# PX4FMUv2_4_6_0.net
KiCad netlist of a schematic drawn in Altium Designer
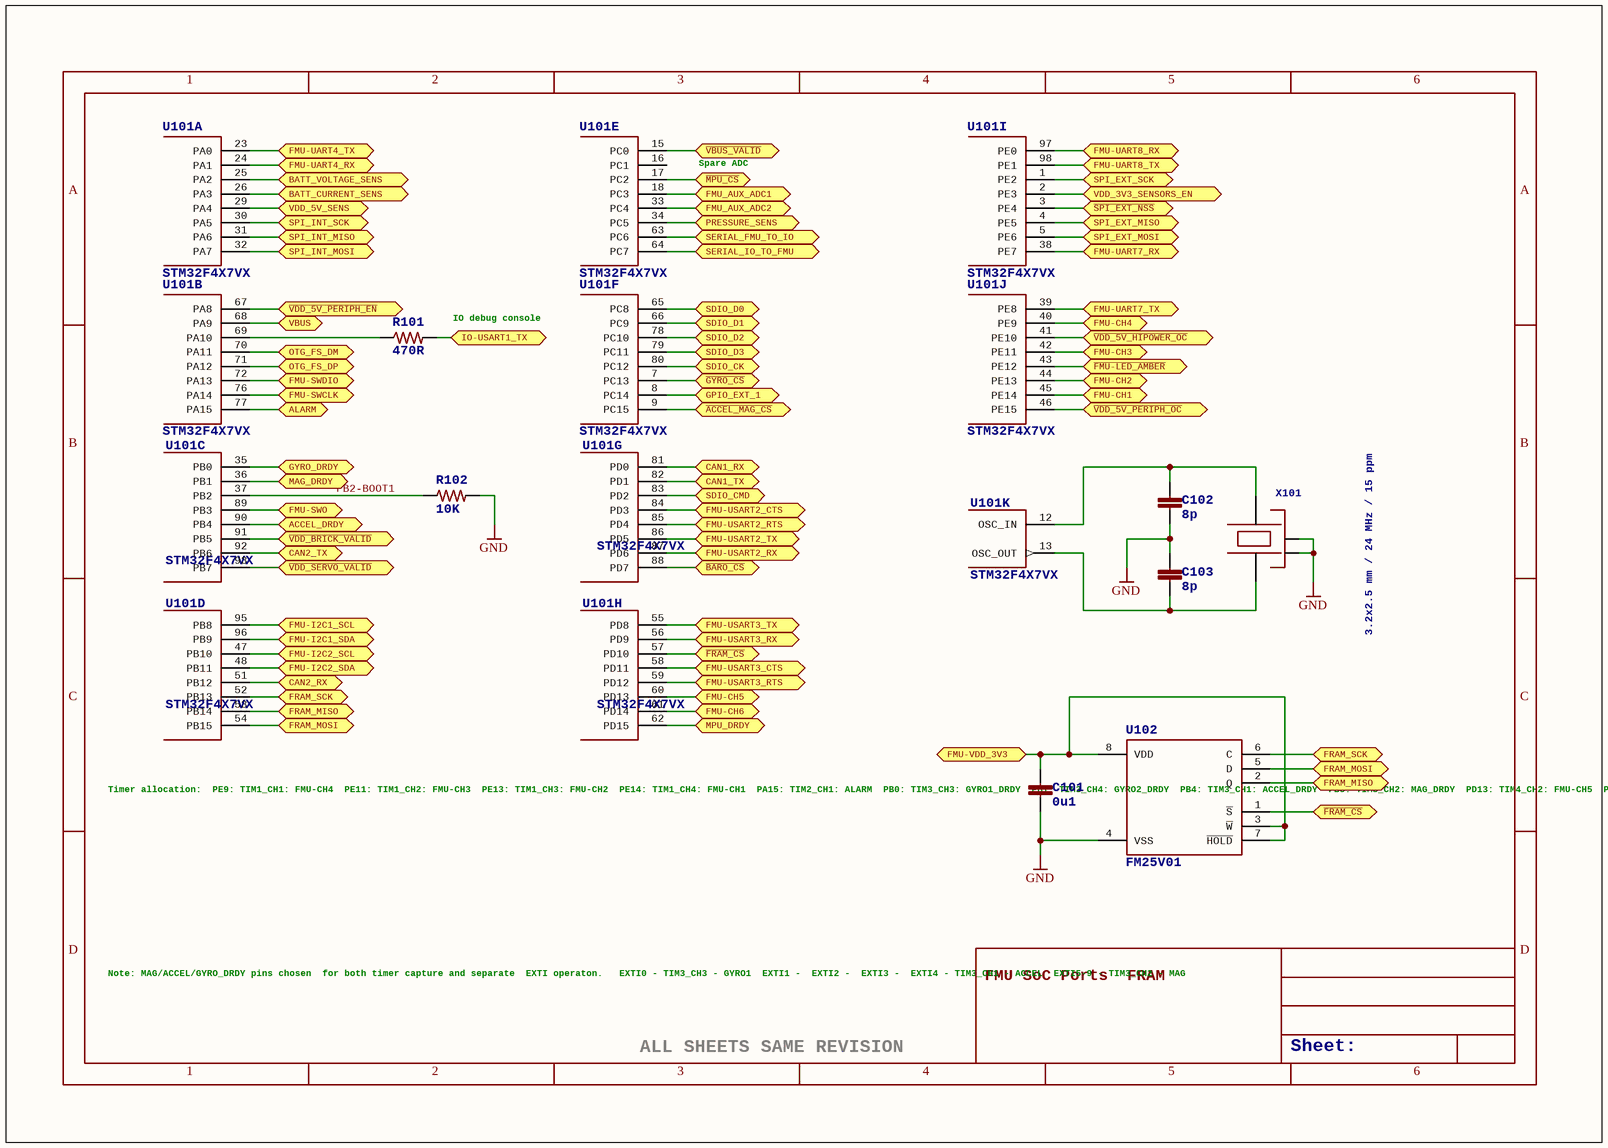
[diagram p0: PX4FMUv2.4.6_0.SchDoc]

(export (version "E")
  (design (tool "Eeschema 10.0.6"))
  (components
    (comp (ref "C101")
      (value "0u1")
      (footprint "0402-CAP")
      (description "CapacitorStandard 0603 ceramic capacitor, and 0.1\" leaded capacitor.")
      (fields (field (name "PARTNO") "CC0402ZRY5V7BB104"))
      (libsource (lib "pixhawk2") (part "CAP0402"))
    )
    (comp (ref "C102")
      (value "8p")
      (footprint "0402-CAP")
      (description "CapacitorStandard 0603 ceramic capacitor, and 0.1\" leaded capacitor.")
      (fields (field (name "PARTNO") "C1005C0G1H080C"))
      (libsource (lib "pixhawk2") (part "CAP0402"))
    )
    (comp (ref "C103")
      (value "8p")
      (footprint "0402-CAP")
      (description "CapacitorStandard 0603 ceramic capacitor, and 0.1\" leaded capacitor.")
      (fields (field (name "PARTNO") "C1005C0G1H080C"))
      (libsource (lib "pixhawk2") (part "CAP0402"))
    )
    (comp (ref "R101")
      (value "470R")
      (footprint "0402-RES")
      (fields (field (name "PARTNO") "RC0402FR-07470RL"))
      (libsource (lib "pixhawk2") (part "RESISTOR0402-RES"))
    )
    (comp (ref "R102")
      (value "10K")
      (footprint "0402-RES")
      (fields (field (name "PARTNO") "RC0402FR-0710KL"))
      (libsource (lib "pixhawk2") (part "RESISTOR0402-RES"))
    )
    (comp (ref "U101")
      (value "STM32F4X7VX")
      (footprint "TQFP100")
      (fields (field (name "PARTNO") "STM32F427VI"))
      (libsource (lib "pixhawk2") (part "STM32F4X7VX"))
    )
    (comp (ref "U102")
      (value "FM25V01")
      (footprint "SO08")
      (description "FM25V01 128Kb Serial 3V F-RAM Memory")
      (fields (field (name "PARTNO") "FM25V01-G"))
      (libsource (lib "pixhawk2") (part "FM25V01"))
    )
    (comp (ref "X101")
      (value "3.2x2.5 mm / 24 MHz / 15 ppm")
      (footprint "OSCILLATOR-3.2X2.5")
      (description "Crystal Oscillator in 3.2x2.5 SMD")
      (libsource (lib "pixhawk2") (part "OSCILLATOR-3.2X2.5"))
    )
  )
  (nets
    (net (code "1") (name "/ACCEL_DRDY") (class "Default")
      (node (ref "U101") (pin "90") (pinfunction "PB4_90") (pintype "passive"))
    )
    (net (code "2") (name "/ALARM") (class "Default")
      (node (ref "U101") (pin "77") (pinfunction "PA15_77") (pintype "passive"))
    )
    (net (code "3") (name "/BATT_CURRENT_SENS") (class "Default")
      (node (ref "U101") (pin "26") (pinfunction "PA3_26") (pintype "passive"))
    )
    (net (code "4") (name "/BATT_VOLTAGE_SENS") (class "Default")
      (node (ref "U101") (pin "25") (pinfunction "PA2_25") (pintype "passive"))
    )
    (net (code "5") (name "/CAN1_RX") (class "Default")
      (node (ref "U101") (pin "81") (pinfunction "PD0_81") (pintype "passive"))
    )
    (net (code "6") (name "/CAN1_TX") (class "Default")
      (node (ref "U101") (pin "82") (pinfunction "PD1_82") (pintype "passive"))
    )
    (net (code "7") (name "/CAN2_RX") (class "Default")
      (node (ref "U101") (pin "51") (pinfunction "PB12_51") (pintype "passive"))
    )
    (net (code "8") (name "/CAN2_TX") (class "Default")
      (node (ref "U101") (pin "92") (pinfunction "PB6_92") (pintype "passive"))
    )
    (net (code "9") (name "/FMU-CH1") (class "Default")
      (node (ref "U101") (pin "45") (pinfunction "PE14_45") (pintype "passive"))
    )
    (net (code "10") (name "/FMU-CH2") (class "Default")
      (node (ref "U101") (pin "44") (pinfunction "PE13_44") (pintype "passive"))
    )
    (net (code "11") (name "/FMU-CH3") (class "Default")
      (node (ref "U101") (pin "42") (pinfunction "PE11_42") (pintype "passive"))
    )
    (net (code "12") (name "/FMU-CH4") (class "Default")
      (node (ref "U101") (pin "40") (pinfunction "PE9_40") (pintype "passive"))
    )
    (net (code "13") (name "/FMU-CH5") (class "Default")
      (node (ref "U101") (pin "60") (pinfunction "PD13_60") (pintype "passive"))
    )
    (net (code "14") (name "/FMU-CH6") (class "Default")
      (node (ref "U101") (pin "61") (pinfunction "PD14_61") (pintype "passive"))
    )
    (net (code "15") (name "/FMU-I2C1_SCL") (class "Default")
      (node (ref "U101") (pin "95") (pinfunction "PB8_95") (pintype "passive"))
    )
    (net (code "16") (name "/FMU-I2C1_SDA") (class "Default")
      (node (ref "U101") (pin "96") (pinfunction "PB9_96") (pintype "passive"))
    )
    (net (code "17") (name "/FMU-I2C2_SCL") (class "Default")
      (node (ref "U101") (pin "47") (pinfunction "PB10_47") (pintype "passive"))
    )
    (net (code "18") (name "/FMU-I2C2_SDA") (class "Default")
      (node (ref "U101") (pin "48") (pinfunction "PB11_48") (pintype "passive"))
    )
    (net (code "19") (name "/FMU-SWCLK") (class "Default")
      (node (ref "U101") (pin "76") (pinfunction "PA14_76") (pintype "passive"))
    )
    (net (code "20") (name "/FMU-SWDIO") (class "Default")
      (node (ref "U101") (pin "72") (pinfunction "PA13_72") (pintype "passive"))
    )
    (net (code "21") (name "/FMU-SWO") (class "Default")
      (node (ref "U101") (pin "89") (pinfunction "PB3_89") (pintype "passive"))
    )
    (net (code "22") (name "/FMU-UART4_RX") (class "Default")
      (node (ref "U101") (pin "24") (pinfunction "PA1_24") (pintype "passive"))
    )
    (net (code "23") (name "/FMU-UART4_TX") (class "Default")
      (node (ref "U101") (pin "23") (pinfunction "PA0_23") (pintype "passive"))
    )
    (net (code "24") (name "/FMU-UART7_RX") (class "Default")
      (node (ref "U101") (pin "38") (pinfunction "PE7_38") (pintype "passive"))
    )
    (net (code "25") (name "/FMU-UART7_TX") (class "Default")
      (node (ref "U101") (pin "39") (pinfunction "PE8_39") (pintype "passive"))
    )
    (net (code "26") (name "/FMU-UART8_RX") (class "Default")
      (node (ref "U101") (pin "97") (pinfunction "PE0_97") (pintype "passive"))
    )
    (net (code "27") (name "/FMU-UART8_TX") (class "Default")
      (node (ref "U101") (pin "98") (pinfunction "PE1_98") (pintype "passive"))
    )
    (net (code "28") (name "/FMU-USART2_CTS") (class "Default")
      (node (ref "U101") (pin "84") (pinfunction "PD3_84") (pintype "passive"))
    )
    (net (code "29") (name "/FMU-USART2_RTS") (class "Default")
      (node (ref "U101") (pin "85") (pinfunction "PD4_85") (pintype "passive"))
    )
    (net (code "30") (name "/FMU-USART2_RX") (class "Default")
      (node (ref "U101") (pin "87") (pinfunction "PD6_87") (pintype "passive"))
    )
    (net (code "31") (name "/FMU-USART2_TX") (class "Default")
      (node (ref "U101") (pin "86") (pinfunction "PD5_86") (pintype "passive"))
    )
    (net (code "32") (name "/FMU-USART3_CTS") (class "Default")
      (node (ref "U101") (pin "58") (pinfunction "PD11_58") (pintype "passive"))
    )
    (net (code "33") (name "/FMU-USART3_RTS") (class "Default")
      (node (ref "U101") (pin "59") (pinfunction "PD12_59") (pintype "passive"))
    )
    (net (code "34") (name "/FMU-USART3_RX") (class "Default")
      (node (ref "U101") (pin "56") (pinfunction "PD9_56") (pintype "passive"))
    )
    (net (code "35") (name "/FMU-USART3_TX") (class "Default")
      (node (ref "U101") (pin "55") (pinfunction "PD8_55") (pintype "passive"))
    )
    (net (code "36") (name "/FMU-VDD_3V3") (class "Default")
      (node (ref "C101") (pin "P$1") (pinfunction "1_P$1") (pintype "passive"))
      (node (ref "U102") (pin "3") (pinfunction "~{W}_3") (pintype "passive"))
      (node (ref "U102") (pin "7") (pinfunction "~{HOLD}_7") (pintype "passive"))
      (node (ref "U102") (pin "8") (pinfunction "VDD_8") (pintype "passive"))
    )
    (net (code "37") (name "/FMU_AUX_ADC1") (class "Default")
      (node (ref "U101") (pin "18") (pinfunction "PC3_18") (pintype "passive"))
    )
    (net (code "38") (name "/FMU_AUX_ADC2") (class "Default")
      (node (ref "U101") (pin "33") (pinfunction "PC4_33") (pintype "passive"))
    )
    (net (code "39") (name "/FRAM_MISO") (class "Default")
      (node (ref "U101") (pin "53") (pinfunction "PB14_53") (pintype "passive"))
      (node (ref "U102") (pin "2") (pinfunction "Q_2") (pintype "passive"))
    )
    (net (code "40") (name "/FRAM_MOSI") (class "Default")
      (node (ref "U101") (pin "54") (pinfunction "PB15_54") (pintype "passive"))
      (node (ref "U102") (pin "5") (pinfunction "D_5") (pintype "passive"))
    )
    (net (code "41") (name "/FRAM_SCK") (class "Default")
      (node (ref "U101") (pin "52") (pinfunction "PB13_52") (pintype "passive"))
      (node (ref "U102") (pin "6") (pinfunction "C_6") (pintype "passive"))
    )
    (net (code "42") (name "/GPIO_EXT_1") (class "Default")
      (node (ref "U101") (pin "8") (pinfunction "PC14_8") (pintype "passive"))
    )
    (net (code "43") (name "/GYRO_DRDY") (class "Default")
      (node (ref "U101") (pin "35") (pinfunction "PB0_35") (pintype "passive"))
    )
    (net (code "44") (name "/IO-USART1_TX") (class "Default")
      (node (ref "R101") (pin "P$2") (pinfunction "2_P$2") (pintype "passive"))
    )
    (net (code "45") (name "/MAG_DRDY") (class "Default")
      (node (ref "U101") (pin "36") (pinfunction "PB1_36") (pintype "passive"))
    )
    (net (code "46") (name "/MPU_DRDY") (class "Default")
      (node (ref "U101") (pin "62") (pinfunction "PD15_62") (pintype "passive"))
    )
    (net (code "47") (name "/OTG_FS_DM") (class "Default")
      (node (ref "U101") (pin "70") (pinfunction "PA11_70") (pintype "passive"))
    )
    (net (code "48") (name "/OTG_FS_DP") (class "Default")
      (node (ref "U101") (pin "71") (pinfunction "PA12_71") (pintype "passive"))
    )
    (net (code "49") (name "/PB2-BOOT1") (class "Default")
      (node (ref "R102") (pin "P$1") (pinfunction "1_P$1") (pintype "passive"))
      (node (ref "U101") (pin "37") (pinfunction "PB2_37") (pintype "passive"))
    )
    (net (code "50") (name "/PRESSURE_SENS") (class "Default")
      (node (ref "U101") (pin "34") (pinfunction "PC5_34") (pintype "passive"))
    )
    (net (code "51") (name "/SDIO_CK") (class "Default")
      (node (ref "U101") (pin "80") (pinfunction "PC12_80") (pintype "passive"))
    )
    (net (code "52") (name "/SDIO_CMD") (class "Default")
      (node (ref "U101") (pin "83") (pinfunction "PD2_83") (pintype "passive"))
    )
    (net (code "53") (name "/SDIO_D0") (class "Default")
      (node (ref "U101") (pin "65") (pinfunction "PC8_65") (pintype "passive"))
    )
    (net (code "54") (name "/SDIO_D1") (class "Default")
      (node (ref "U101") (pin "66") (pinfunction "PC9_66") (pintype "passive"))
    )
    (net (code "55") (name "/SDIO_D2") (class "Default")
      (node (ref "U101") (pin "78") (pinfunction "PC10_78") (pintype "passive"))
    )
    (net (code "56") (name "/SDIO_D3") (class "Default")
      (node (ref "U101") (pin "79") (pinfunction "PC11_79") (pintype "passive"))
    )
    (net (code "57") (name "/SERIAL_FMU_TO_IO") (class "Default")
      (node (ref "U101") (pin "63") (pinfunction "PC6_63") (pintype "passive"))
    )
    (net (code "58") (name "/SERIAL_IO_TO_FMU") (class "Default")
      (node (ref "U101") (pin "64") (pinfunction "PC7_64") (pintype "passive"))
    )
    (net (code "59") (name "/SPI_EXT_MISO") (class "Default")
      (node (ref "U101") (pin "4") (pinfunction "PE5_4") (pintype "passive"))
    )
    (net (code "60") (name "/SPI_EXT_MOSI") (class "Default")
      (node (ref "U101") (pin "5") (pinfunction "PE6_5") (pintype "passive"))
    )
    (net (code "61") (name "/SPI_EXT_SCK") (class "Default")
      (node (ref "U101") (pin "1") (pinfunction "PE2_1") (pintype "passive"))
    )
    (net (code "62") (name "/SPI_INT_MISO") (class "Default")
      (node (ref "U101") (pin "31") (pinfunction "PA6_31") (pintype "passive"))
    )
    (net (code "63") (name "/SPI_INT_MOSI") (class "Default")
      (node (ref "U101") (pin "32") (pinfunction "PA7_32") (pintype "passive"))
    )
    (net (code "64") (name "/SPI_INT_SCK") (class "Default")
      (node (ref "U101") (pin "30") (pinfunction "PA5_30") (pintype "passive"))
    )
    (net (code "65") (name "/VBUS") (class "Default")
      (node (ref "U101") (pin "68") (pinfunction "PA9_68") (pintype "passive"))
    )
    (net (code "66") (name "/VDD_3V3_SENSORS_EN") (class "Default")
      (node (ref "U101") (pin "2") (pinfunction "PE3_2") (pintype "passive"))
    )
    (net (code "67") (name "/VDD_5V_SENS") (class "Default")
      (node (ref "U101") (pin "29") (pinfunction "PA4_29") (pintype "passive"))
    )
    (net (code "68") (name "/~{ACCEL_MAG_CS}") (class "Default")
      (node (ref "U101") (pin "9") (pinfunction "PC15_9") (pintype "passive"))
    )
    (net (code "69") (name "/~{BARO_CS}") (class "Default")
      (node (ref "U101") (pin "88") (pinfunction "PD7_88") (pintype "passive"))
    )
    (net (code "70") (name "/~{FMU-LED_AMBER}") (class "Default")
      (node (ref "U101") (pin "43") (pinfunction "PE12_43") (pintype "passive"))
    )
    (net (code "71") (name "/~{FRAM_CS}") (class "Default")
      (node (ref "U101") (pin "57") (pinfunction "PD10_57") (pintype "passive"))
      (node (ref "U102") (pin "1") (pinfunction "~{S}_1") (pintype "passive"))
    )
    (net (code "72") (name "/~{GYRO_CS}") (class "Default")
      (node (ref "U101") (pin "7") (pinfunction "PC13_7") (pintype "passive"))
    )
    (net (code "73") (name "/~{MPU_CS}") (class "Default")
      (node (ref "U101") (pin "17") (pinfunction "PC2_17") (pintype "passive"))
    )
    (net (code "74") (name "/~{SPI_EXT_NSS}") (class "Default")
      (node (ref "U101") (pin "3") (pinfunction "PE4_3") (pintype "passive"))
    )
    (net (code "75") (name "/~{VBUS_VALID}") (class "Default")
      (node (ref "U101") (pin "15") (pinfunction "PC0_15") (pintype "passive"))
    )
    (net (code "76") (name "/~{VDD_5V_HIPOWER_OC}") (class "Default")
      (node (ref "U101") (pin "41") (pinfunction "PE10_41") (pintype "passive"))
    )
    (net (code "77") (name "/~{VDD_5V_PERIPH_EN}") (class "Default")
      (node (ref "U101") (pin "67") (pinfunction "PA8_67") (pintype "passive"))
    )
    (net (code "78") (name "/~{VDD_5V_PERIPH_OC}") (class "Default")
      (node (ref "U101") (pin "46") (pinfunction "PE15_46") (pintype "passive"))
    )
    (net (code "79") (name "/~{VDD_BRICK_VALID}") (class "Default")
      (node (ref "U101") (pin "91") (pinfunction "PB5_91") (pintype "passive"))
    )
    (net (code "80") (name "/~{VDD_SERVO_VALID}") (class "Default")
      (node (ref "U101") (pin "93") (pinfunction "PB7_93") (pintype "passive"))
    )
    (net (code "81") (name "GND") (class "Default")
      (node (ref "C101") (pin "P$2") (pinfunction "2_P$2") (pintype "passive"))
      (node (ref "C102") (pin "P$2") (pinfunction "2_P$2") (pintype "passive"))
      (node (ref "C103") (pin "P$1") (pinfunction "1_P$1") (pintype "passive"))
      (node (ref "R102") (pin "P$2") (pinfunction "2_P$2") (pintype "passive"))
      (node (ref "U102") (pin "4") (pinfunction "VSS_4") (pintype "passive"))
      (node (ref "X101") (pin "2") (pinfunction "NC_2_2") (pintype "open_emitter"))
      (node (ref "X101") (pin "4") (pinfunction "NC_4_4") (pintype "open_emitter"))
    )
    (net (code "82") (name "Net-(C102-1)") (class "Default")
      (node (ref "C102") (pin "P$1") (pinfunction "1_P$1") (pintype "passive"))
      (node (ref "U101") (pin "12") (pinfunction "OSC_IN_12") (pintype "passive"))
      (node (ref "X101") (pin "3") (pinfunction "3_3") (pintype "passive"))
    )
    (net (code "83") (name "Net-(C103-2)") (class "Default")
      (node (ref "C103") (pin "P$2") (pinfunction "2_P$2") (pintype "passive"))
      (node (ref "U101") (pin "13") (pinfunction "OSC_OUT_13") (pintype "output"))
      (node (ref "X101") (pin "1") (pinfunction "1_1") (pintype "passive"))
    )
    (net (code "84") (name "Net-(R101-1)") (class "Default")
      (node (ref "R101") (pin "P$1") (pinfunction "1_P$1") (pintype "passive"))
      (node (ref "U101") (pin "69") (pinfunction "PA10_69") (pintype "passive"))
    )
    (net (code "85") (name "unconnected-(U101E-PC1-Pad16)") (class "Default")
      (node (ref "U101") (pin "16") (pinfunction "PC1_16") (pintype "passive"))
    )
  )
)
